# S7CAS-PLEIADES-CARTE-MERE_P07_CLOCK.net
KiCad netlist of a schematic drawn in Altium Designer
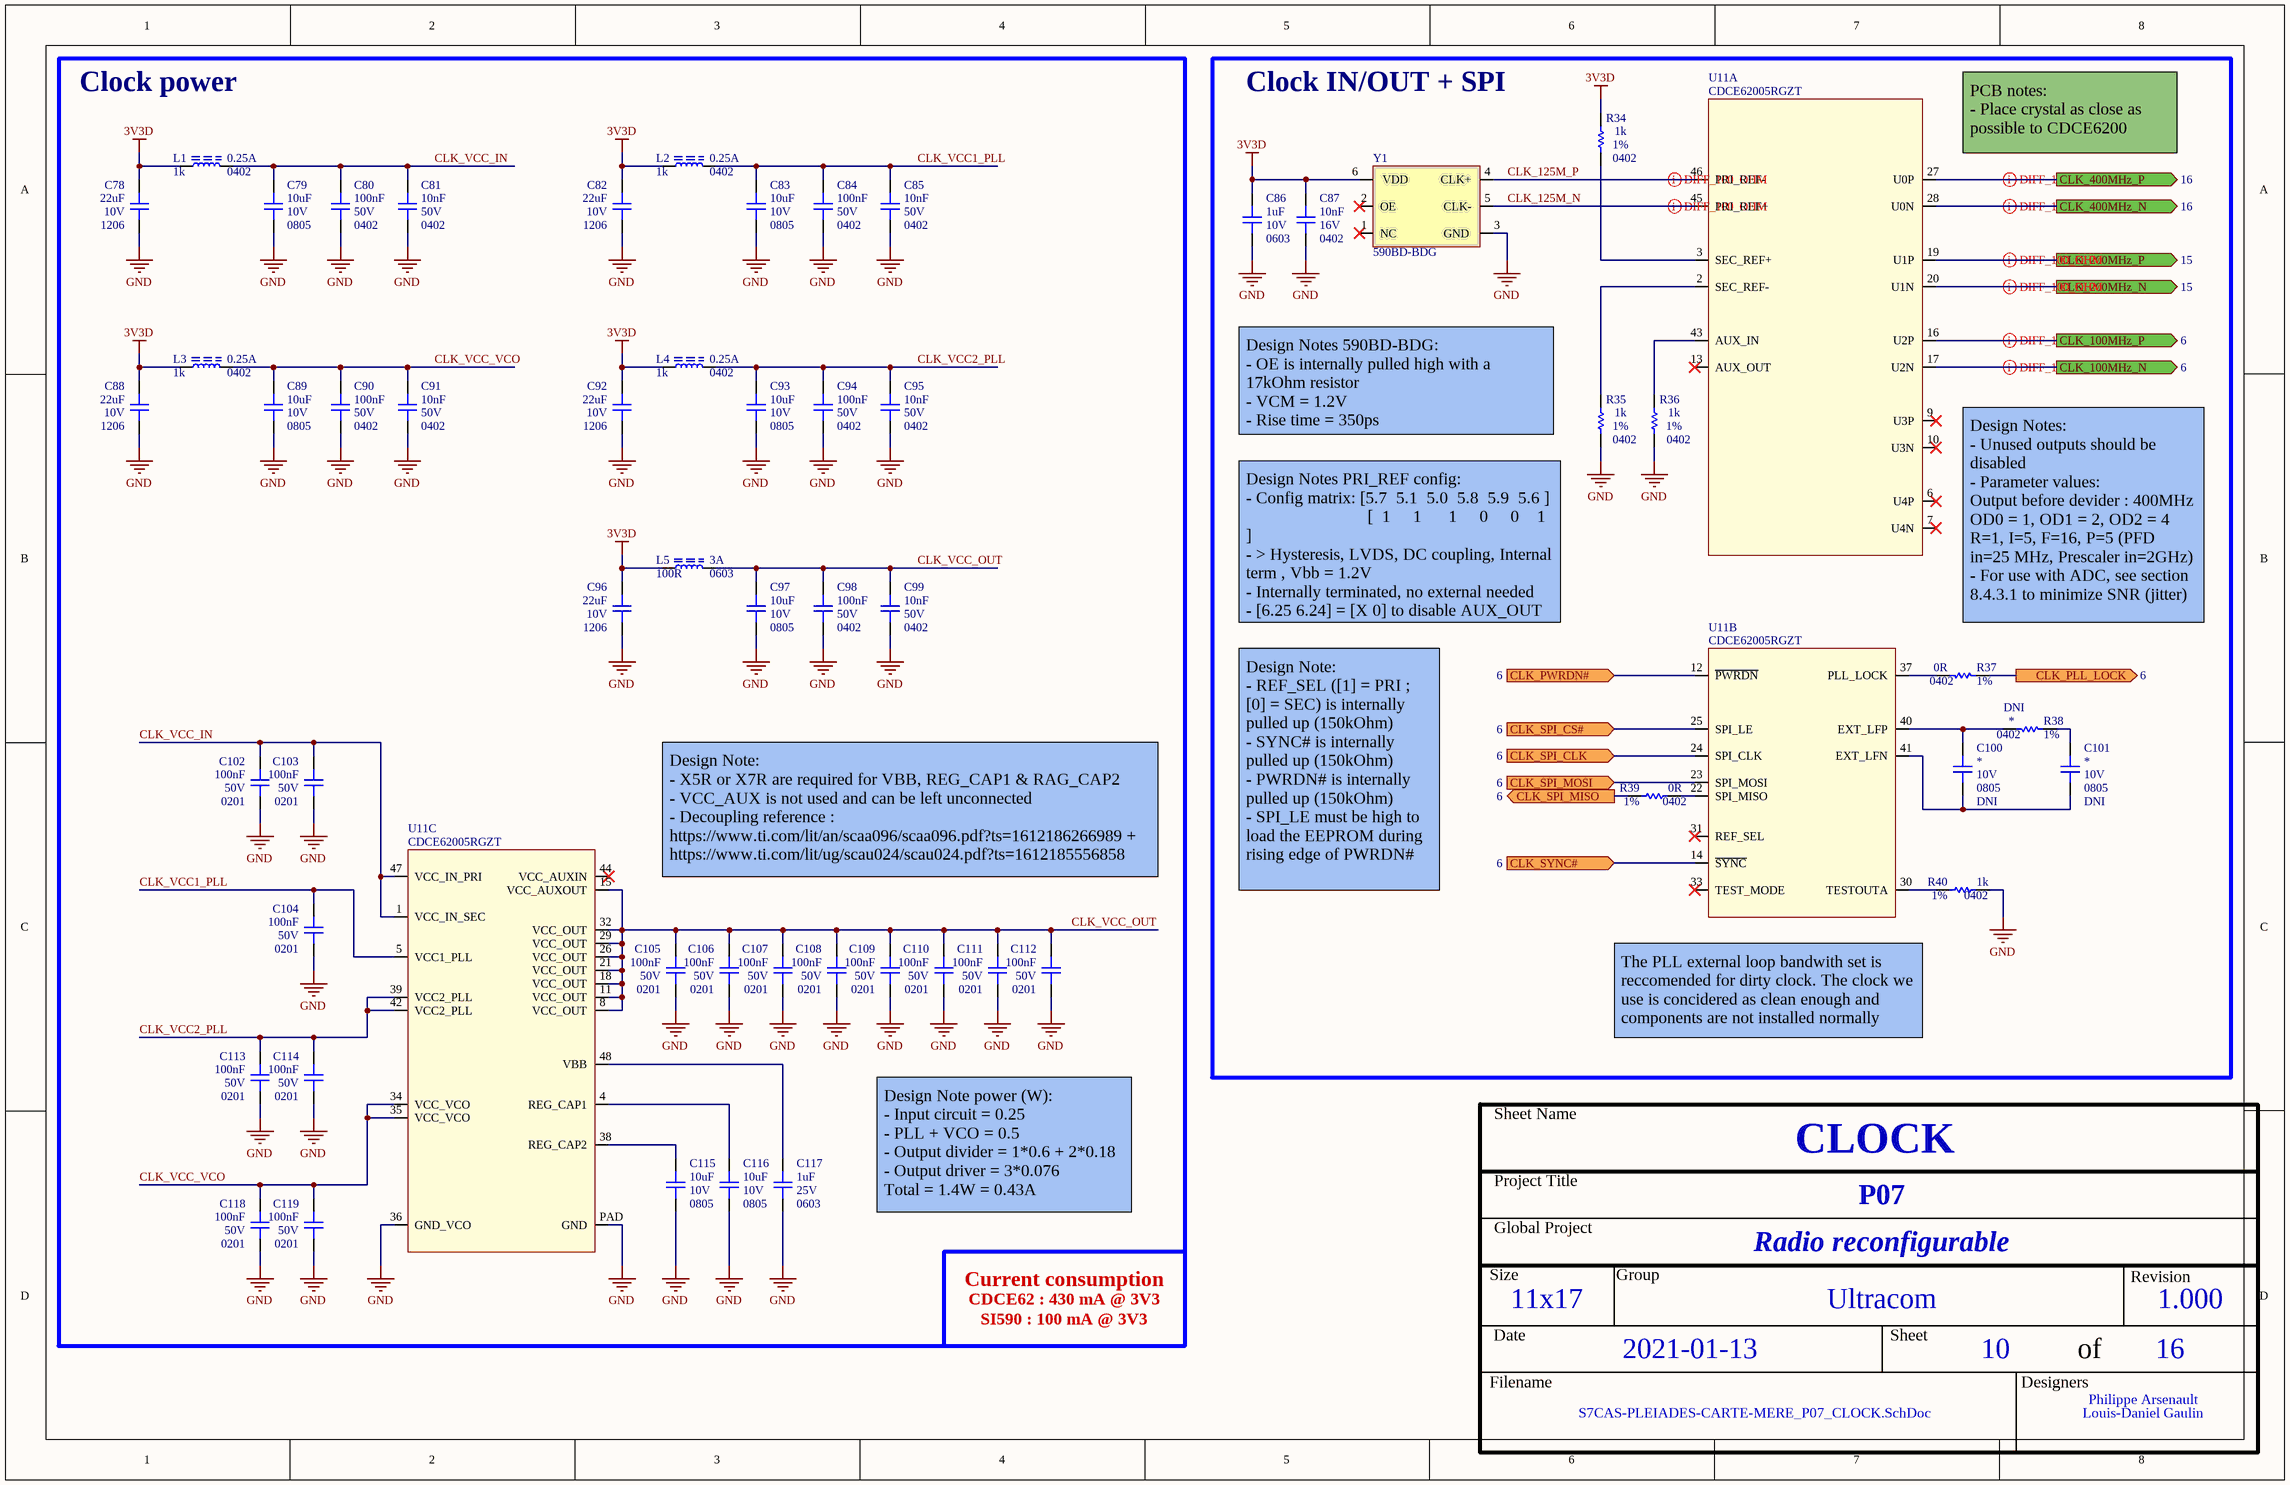
[diagram p0: S7CAS-PLEIADES-CARTE-MERE_P07_CLOCK.SchDoc]

(export (version "E")
  (design (tool "Eeschema 10.0.6"))
  (components
    (comp (ref "C78")
      (value "22uF")
      (footprint "CAP_1206")
      (description "CAP - 1206")
      (fields
        (field (name "VOLTAGE") "10V")
        (field (name "PACKAGE") "1206")
        (field (name "CREATEDBY") "Jonathan Bouchard")
      )
      (libsource (lib "S7CAS_LIB2021") (part "CAP - 1206"))
    )
    (comp (ref "C79")
      (value "10uF")
      (footprint "CAP_0805")
      (description "CAP - 0805")
      (fields
        (field (name "MFG") "CL21B106KPQNNNE")
        (field (name "VOLTAGE") "10V")
        (field (name "PACKAGE") "0805")
        (field (name "CREATEDBY") "Jonathan Bouchard")
      )
      (libsource (lib "S7CAS_LIB2021") (part "CAP - 0805"))
    )
    (comp (ref "C80")
      (value "100nF")
      (footprint "CAP_0402")
      (description "CAP - 0402")
      (fields
        (field (name "VOLTAGE") "50V")
        (field (name "PACKAGE") "0402")
        (field (name "CREATEDBY") "Jonathan Bouchard")
      )
      (libsource (lib "S7CAS_LIB2021") (part "CAP - 0402"))
    )
    (comp (ref "C81")
      (value "10nF")
      (footprint "CAP_0402")
      (description "CAP - 0402")
      (fields
        (field (name "VOLTAGE") "50V")
        (field (name "PACKAGE") "0402")
        (field (name "CREATEDBY") "Jonathan Bouchard")
      )
      (libsource (lib "S7CAS_LIB2021") (part "CAP - 0402"))
    )
    (comp (ref "C82")
      (value "22uF")
      (footprint "CAP_1206")
      (description "CAP - 1206")
      (fields
        (field (name "VOLTAGE") "10V")
        (field (name "PACKAGE") "1206")
        (field (name "CREATEDBY") "Jonathan Bouchard")
      )
      (libsource (lib "S7CAS_LIB2021") (part "CAP - 1206"))
    )
    (comp (ref "C83")
      (value "10uF")
      (footprint "CAP_0805")
      (description "CAP - 0805")
      (fields
        (field (name "MFG") "CL21B106KPQNNNE")
        (field (name "VOLTAGE") "10V")
        (field (name "PACKAGE") "0805")
        (field (name "CREATEDBY") "Jonathan Bouchard")
      )
      (libsource (lib "S7CAS_LIB2021") (part "CAP - 0805"))
    )
    (comp (ref "C84")
      (value "100nF")
      (footprint "CAP_0402")
      (description "CAP - 0402")
      (fields
        (field (name "VOLTAGE") "50V")
        (field (name "PACKAGE") "0402")
        (field (name "CREATEDBY") "Jonathan Bouchard")
      )
      (libsource (lib "S7CAS_LIB2021") (part "CAP - 0402"))
    )
    (comp (ref "C85")
      (value "10nF")
      (footprint "CAP_0402")
      (description "CAP - 0402")
      (fields
        (field (name "VOLTAGE") "50V")
        (field (name "PACKAGE") "0402")
        (field (name "CREATEDBY") "Jonathan Bouchard")
      )
      (libsource (lib "S7CAS_LIB2021") (part "CAP - 0402"))
    )
    (comp (ref "C86")
      (value "1uF")
      (footprint "CAP_0603")
      (description "CAP - 0603")
      (fields
        (field (name "VOLTAGE") "10V")
        (field (name "PACKAGE") "0603")
        (field (name "CREATEDBY") "Jonathan Bouchard")
      )
      (libsource (lib "S7CAS_LIB2021") (part "CAP - 0603"))
    )
    (comp (ref "C87")
      (value "10nF")
      (footprint "CAP_0402")
      (description "CAP - 0402")
      (fields
        (field (name "VOLTAGE") "16V")
        (field (name "PACKAGE") "0402")
        (field (name "CREATEDBY") "Jonathan Bouchard")
      )
      (libsource (lib "S7CAS_LIB2021") (part "CAP - 0402"))
    )
    (comp (ref "C88")
      (value "22uF")
      (footprint "CAP_1206")
      (description "CAP - 1206")
      (fields
        (field (name "VOLTAGE") "10V")
        (field (name "PACKAGE") "1206")
        (field (name "CREATEDBY") "Jonathan Bouchard")
      )
      (libsource (lib "S7CAS_LIB2021") (part "CAP - 1206"))
    )
    (comp (ref "C89")
      (value "10uF")
      (footprint "CAP_0805")
      (description "CAP - 0805")
      (fields
        (field (name "MFG") "CL21B106KPQNNNE")
        (field (name "VOLTAGE") "10V")
        (field (name "PACKAGE") "0805")
        (field (name "CREATEDBY") "Jonathan Bouchard")
      )
      (libsource (lib "S7CAS_LIB2021") (part "CAP - 0805"))
    )
    (comp (ref "C90")
      (value "100nF")
      (footprint "CAP_0402")
      (description "CAP - 0402")
      (fields
        (field (name "VOLTAGE") "50V")
        (field (name "PACKAGE") "0402")
        (field (name "CREATEDBY") "Jonathan Bouchard")
      )
      (libsource (lib "S7CAS_LIB2021") (part "CAP - 0402"))
    )
    (comp (ref "C91")
      (value "10nF")
      (footprint "CAP_0402")
      (description "CAP - 0402")
      (fields
        (field (name "VOLTAGE") "50V")
        (field (name "PACKAGE") "0402")
        (field (name "CREATEDBY") "Jonathan Bouchard")
      )
      (libsource (lib "S7CAS_LIB2021") (part "CAP - 0402"))
    )
    (comp (ref "C92")
      (value "22uF")
      (footprint "CAP_1206")
      (description "CAP - 1206")
      (fields
        (field (name "VOLTAGE") "10V")
        (field (name "PACKAGE") "1206")
        (field (name "CREATEDBY") "Jonathan Bouchard")
      )
      (libsource (lib "S7CAS_LIB2021") (part "CAP - 1206"))
    )
    (comp (ref "C93")
      (value "10uF")
      (footprint "CAP_0805")
      (description "CAP - 0805")
      (fields
        (field (name "MFG") "CL21B106KPQNNNE")
        (field (name "VOLTAGE") "10V")
        (field (name "PACKAGE") "0805")
        (field (name "CREATEDBY") "Jonathan Bouchard")
      )
      (libsource (lib "S7CAS_LIB2021") (part "CAP - 0805"))
    )
    (comp (ref "C94")
      (value "100nF")
      (footprint "CAP_0402")
      (description "CAP - 0402")
      (fields
        (field (name "VOLTAGE") "50V")
        (field (name "PACKAGE") "0402")
        (field (name "CREATEDBY") "Jonathan Bouchard")
      )
      (libsource (lib "S7CAS_LIB2021") (part "CAP - 0402"))
    )
    (comp (ref "C95")
      (value "10nF")
      (footprint "CAP_0402")
      (description "CAP - 0402")
      (fields
        (field (name "VOLTAGE") "50V")
        (field (name "PACKAGE") "0402")
        (field (name "CREATEDBY") "Jonathan Bouchard")
      )
      (libsource (lib "S7CAS_LIB2021") (part "CAP - 0402"))
    )
    (comp (ref "C96")
      (value "22uF")
      (footprint "CAP_1206")
      (description "CAP - 1206")
      (fields
        (field (name "VOLTAGE") "10V")
        (field (name "PACKAGE") "1206")
        (field (name "CREATEDBY") "Jonathan Bouchard")
      )
      (libsource (lib "S7CAS_LIB2021") (part "CAP - 1206"))
    )
    (comp (ref "C97")
      (value "10uF")
      (footprint "CAP_0805")
      (description "CAP - 0805")
      (fields
        (field (name "MFG") "CL21B106KPQNNNE")
        (field (name "VOLTAGE") "10V")
        (field (name "PACKAGE") "0805")
        (field (name "CREATEDBY") "Jonathan Bouchard")
      )
      (libsource (lib "S7CAS_LIB2021") (part "CAP - 0805"))
    )
    (comp (ref "C98")
      (value "100nF")
      (footprint "CAP_0402")
      (description "CAP - 0402")
      (fields
        (field (name "VOLTAGE") "50V")
        (field (name "PACKAGE") "0402")
        (field (name "CREATEDBY") "Jonathan Bouchard")
      )
      (libsource (lib "S7CAS_LIB2021") (part "CAP - 0402"))
    )
    (comp (ref "C99")
      (value "10nF")
      (footprint "CAP_0402")
      (description "CAP - 0402")
      (fields
        (field (name "VOLTAGE") "50V")
        (field (name "PACKAGE") "0402")
        (field (name "CREATEDBY") "Jonathan Bouchard")
      )
      (libsource (lib "S7CAS_LIB2021") (part "CAP - 0402"))
    )
    (comp (ref "C100")
      (value "CAP - 0805")
      (footprint "CAP_0805")
      (fields
        (field (name "MFG") "CL21B106KPQNNNE")
        (field (name "VOLTAGE") "10V")
        (field (name "NI") "DNI")
        (field (name "PACKAGE") "0805")
        (field (name "ALTIUM_VALUE") "*")
        (field (name "CREATEDBY") "Jonathan Bouchard")
      )
      (libsource (lib "S7CAS_LIB2021") (part "CAP - 0805"))
    )
    (comp (ref "C101")
      (value "CAP - 0805")
      (footprint "CAP_0805")
      (fields
        (field (name "MFG") "CL21B106KPQNNNE")
        (field (name "VOLTAGE") "10V")
        (field (name "NI") "DNI")
        (field (name "PACKAGE") "0805")
        (field (name "ALTIUM_VALUE") "*")
        (field (name "CREATEDBY") "Jonathan Bouchard")
      )
      (libsource (lib "S7CAS_LIB2021") (part "CAP - 0805"))
    )
    (comp (ref "C102")
      (value "100nF")
      (footprint "CAP_0201")
      (description "CAP - 0201")
      (fields
        (field (name "VOLTAGE") "50V")
        (field (name "PACKAGE") "0201")
        (field (name "CREATEDBY") "Jonathan Bouchard")
      )
      (libsource (lib "S7CAS_LIB2021") (part "CAP - 0201"))
    )
    (comp (ref "C103")
      (value "100nF")
      (footprint "CAP_0201")
      (description "CAP - 0201")
      (fields
        (field (name "VOLTAGE") "50V")
        (field (name "PACKAGE") "0201")
        (field (name "CREATEDBY") "Jonathan Bouchard")
      )
      (libsource (lib "S7CAS_LIB2021") (part "CAP - 0201"))
    )
    (comp (ref "C104")
      (value "100nF")
      (footprint "CAP_0201")
      (description "CAP - 0201")
      (fields
        (field (name "VOLTAGE") "50V")
        (field (name "PACKAGE") "0201")
        (field (name "CREATEDBY") "Jonathan Bouchard")
      )
      (libsource (lib "S7CAS_LIB2021") (part "CAP - 0201"))
    )
    (comp (ref "C105")
      (value "100nF")
      (footprint "CAP_0201")
      (description "CAP - 0201")
      (fields
        (field (name "VOLTAGE") "50V")
        (field (name "PACKAGE") "0201")
        (field (name "CREATEDBY") "Jonathan Bouchard")
      )
      (libsource (lib "S7CAS_LIB2021") (part "CAP - 0201"))
    )
    (comp (ref "C106")
      (value "100nF")
      (footprint "CAP_0201")
      (description "CAP - 0201")
      (fields
        (field (name "VOLTAGE") "50V")
        (field (name "PACKAGE") "0201")
        (field (name "CREATEDBY") "Jonathan Bouchard")
      )
      (libsource (lib "S7CAS_LIB2021") (part "CAP - 0201"))
    )
    (comp (ref "C107")
      (value "100nF")
      (footprint "CAP_0201")
      (description "CAP - 0201")
      (fields
        (field (name "VOLTAGE") "50V")
        (field (name "PACKAGE") "0201")
        (field (name "CREATEDBY") "Jonathan Bouchard")
      )
      (libsource (lib "S7CAS_LIB2021") (part "CAP - 0201"))
    )
    (comp (ref "C108")
      (value "100nF")
      (footprint "CAP_0201")
      (description "CAP - 0201")
      (fields
        (field (name "VOLTAGE") "50V")
        (field (name "PACKAGE") "0201")
        (field (name "CREATEDBY") "Jonathan Bouchard")
      )
      (libsource (lib "S7CAS_LIB2021") (part "CAP - 0201"))
    )
    (comp (ref "C109")
      (value "100nF")
      (footprint "CAP_0201")
      (description "CAP - 0201")
      (fields
        (field (name "VOLTAGE") "50V")
        (field (name "PACKAGE") "0201")
        (field (name "CREATEDBY") "Jonathan Bouchard")
      )
      (libsource (lib "S7CAS_LIB2021") (part "CAP - 0201"))
    )
    (comp (ref "C110")
      (value "100nF")
      (footprint "CAP_0201")
      (description "CAP - 0201")
      (fields
        (field (name "VOLTAGE") "50V")
        (field (name "PACKAGE") "0201")
        (field (name "CREATEDBY") "Jonathan Bouchard")
      )
      (libsource (lib "S7CAS_LIB2021") (part "CAP - 0201"))
    )
    (comp (ref "C111")
      (value "100nF")
      (footprint "CAP_0201")
      (description "CAP - 0201")
      (fields
        (field (name "VOLTAGE") "50V")
        (field (name "PACKAGE") "0201")
        (field (name "CREATEDBY") "Jonathan Bouchard")
      )
      (libsource (lib "S7CAS_LIB2021") (part "CAP - 0201"))
    )
    (comp (ref "C112")
      (value "100nF")
      (footprint "CAP_0201")
      (description "CAP - 0201")
      (fields
        (field (name "VOLTAGE") "50V")
        (field (name "PACKAGE") "0201")
        (field (name "CREATEDBY") "Jonathan Bouchard")
      )
      (libsource (lib "S7CAS_LIB2021") (part "CAP - 0201"))
    )
    (comp (ref "C113")
      (value "100nF")
      (footprint "CAP_0201")
      (description "CAP - 0201")
      (fields
        (field (name "VOLTAGE") "50V")
        (field (name "PACKAGE") "0201")
        (field (name "CREATEDBY") "Jonathan Bouchard")
      )
      (libsource (lib "S7CAS_LIB2021") (part "CAP - 0201"))
    )
    (comp (ref "C114")
      (value "100nF")
      (footprint "CAP_0201")
      (description "CAP - 0201")
      (fields
        (field (name "VOLTAGE") "50V")
        (field (name "PACKAGE") "0201")
        (field (name "CREATEDBY") "Jonathan Bouchard")
      )
      (libsource (lib "S7CAS_LIB2021") (part "CAP - 0201"))
    )
    (comp (ref "C115")
      (value "10uF")
      (footprint "CAP_0805")
      (description "CAP - 0805")
      (fields
        (field (name "MFG") "CL21B106KPQNNNE")
        (field (name "VOLTAGE") "10V")
        (field (name "PACKAGE") "0805")
        (field (name "CREATEDBY") "Jonathan Bouchard")
      )
      (libsource (lib "S7CAS_LIB2021") (part "CAP - 0805"))
    )
    (comp (ref "C116")
      (value "10uF")
      (footprint "CAP_0805")
      (description "CAP - 0805")
      (fields
        (field (name "MFG") "CL21B106KPQNNNE")
        (field (name "VOLTAGE") "10V")
        (field (name "PACKAGE") "0805")
        (field (name "CREATEDBY") "Jonathan Bouchard")
      )
      (libsource (lib "S7CAS_LIB2021") (part "CAP - 0805"))
    )
    (comp (ref "C117")
      (value "1uF")
      (footprint "CAP_0603")
      (description "CAP - 0603")
      (fields
        (field (name "MFG PART NUMBER") "CC0603KRX5R8BB105")
        (field (name "VOLTAGE") "25V")
        (field (name "PACKAGE") "0603")
        (field (name "CREATEDBY") "Jonathan Bouchard")
      )
      (libsource (lib "S7CAS_LIB2021") (part "CAP - 0603"))
    )
    (comp (ref "C118")
      (value "100nF")
      (footprint "CAP_0201")
      (description "CAP - 0201")
      (fields
        (field (name "VOLTAGE") "50V")
        (field (name "PACKAGE") "0201")
        (field (name "CREATEDBY") "Jonathan Bouchard")
      )
      (libsource (lib "S7CAS_LIB2021") (part "CAP - 0201"))
    )
    (comp (ref "C119")
      (value "100nF")
      (footprint "CAP_0201")
      (description "CAP - 0201")
      (fields
        (field (name "VOLTAGE") "50V")
        (field (name "PACKAGE") "0201")
        (field (name "CREATEDBY") "Jonathan Bouchard")
      )
      (libsource (lib "S7CAS_LIB2021") (part "CAP - 0201"))
    )
    (comp (ref "L1")
      (value "1k")
      (footprint "FER_0402")
      (description "FER - 0402")
      (fields
        (field (name "MFG PART NUMBER") "BLM15HD102SN1D")
        (field (name "CURRENT") "0.25A")
        (field (name "PACKAGE") "0402")
        (field (name "CREATEDBY") "Jonathan Bouchard")
      )
      (libsource (lib "S7CAS_LIB2021") (part "FER - 0402"))
    )
    (comp (ref "L2")
      (value "1k")
      (footprint "FER_0402")
      (description "FER - 0402")
      (fields
        (field (name "MFG PART NUMBER") "BLM15HD102SN1D")
        (field (name "CURRENT") "0.25A")
        (field (name "PACKAGE") "0402")
        (field (name "CREATEDBY") "Jonathan Bouchard")
      )
      (libsource (lib "S7CAS_LIB2021") (part "FER - 0402"))
    )
    (comp (ref "L3")
      (value "1k")
      (footprint "FER_0402")
      (description "FER - 0402")
      (fields
        (field (name "MFG PART NUMBER") "BLM15HD102SN1D")
        (field (name "CURRENT") "0.25A")
        (field (name "PACKAGE") "0402")
        (field (name "CREATEDBY") "Jonathan Bouchard")
      )
      (libsource (lib "S7CAS_LIB2021") (part "FER - 0402"))
    )
    (comp (ref "L4")
      (value "1k")
      (footprint "FER_0402")
      (description "FER - 0402")
      (fields
        (field (name "MFG PART NUMBER") "BLM15HD102SN1D")
        (field (name "CURRENT") "0.25A")
        (field (name "PACKAGE") "0402")
        (field (name "CREATEDBY") "Jonathan Bouchard")
      )
      (libsource (lib "S7CAS_LIB2021") (part "FER - 0402"))
    )
    (comp (ref "L5")
      (value "100R")
      (footprint "FER_0603")
      (description "FER - 0603")
      (fields
        (field (name "MFG PART NUMBER") "BLM18KG101TN1D")
        (field (name "CURRENT") "3A")
        (field (name "PACKAGE") "0603")
        (field (name "CREATEDBY") "Jonathan Bouchard")
      )
      (libsource (lib "S7CAS_LIB2021") (part "FER - 0603"))
    )
    (comp (ref "R34")
      (value "1k")
      (footprint "RES_0402")
      (description "RES - 0402")
      (fields
        (field (name "VOLTAGE") "50V")
        (field (name "POWER") "1/16W")
        (field (name "PACKAGE") "0402")
        (field (name "PRECISION") "1%")
        (field (name "CREATEDBY") "Jonathan Bouchard")
      )
      (libsource (lib "S7CAS_LIB2021") (part "RES - 0402"))
    )
    (comp (ref "R35")
      (value "1k")
      (footprint "RES_0402")
      (description "RES - 0402")
      (fields
        (field (name "VOLTAGE") "50V")
        (field (name "POWER") "1/16W")
        (field (name "PACKAGE") "0402")
        (field (name "PRECISION") "1%")
        (field (name "CREATEDBY") "Jonathan Bouchard")
      )
      (libsource (lib "S7CAS_LIB2021") (part "RES - 0402"))
    )
    (comp (ref "R36")
      (value "1k")
      (footprint "RES_0402")
      (description "RES - 0402")
      (fields
        (field (name "VOLTAGE") "50V")
        (field (name "POWER") "1/16W")
        (field (name "PACKAGE") "0402")
        (field (name "PRECISION") "1%")
        (field (name "CREATEDBY") "Jonathan Bouchard")
      )
      (libsource (lib "S7CAS_LIB2021") (part "RES - 0402"))
    )
    (comp (ref "R37")
      (value "0R")
      (footprint "RES_0402")
      (description "RES - 0402")
      (fields
        (field (name "VOLTAGE") "50V")
        (field (name "POWER") "1/16W")
        (field (name "PACKAGE") "0402")
        (field (name "PRECISION") "1%")
        (field (name "CREATEDBY") "Jonathan Bouchard")
      )
      (libsource (lib "S7CAS_LIB2021") (part "RES - 0402"))
    )
    (comp (ref "R38")
      (value "RES - 0402")
      (footprint "RES_0402")
      (fields
        (field (name "VOLTAGE") "50V")
        (field (name "POWER") "1/16W")
        (field (name "NI") "DNI")
        (field (name "PACKAGE") "0402")
        (field (name "PRECISION") "1%")
        (field (name "ALTIUM_VALUE") "*")
        (field (name "CREATEDBY") "Jonathan Bouchard")
      )
      (libsource (lib "S7CAS_LIB2021") (part "RES - 0402"))
    )
    (comp (ref "R39")
      (value "0R")
      (footprint "RES_0402")
      (description "RES - 0402")
      (fields
        (field (name "VOLTAGE") "50V")
        (field (name "POWER") "1/16W")
        (field (name "PACKAGE") "0402")
        (field (name "PRECISION") "1%")
        (field (name "CREATEDBY") "Jonathan Bouchard")
      )
      (libsource (lib "S7CAS_LIB2021") (part "RES - 0402"))
    )
    (comp (ref "R40")
      (value "1k")
      (footprint "RES_0402")
      (description "RES - 0402")
      (fields
        (field (name "VOLTAGE") "50V")
        (field (name "POWER") "1/16W")
        (field (name "PACKAGE") "0402")
        (field (name "PRECISION") "1%")
        (field (name "CREATEDBY") "Jonathan Bouchard")
      )
      (libsource (lib "S7CAS_LIB2021") (part "RES - 0402"))
    )
    (comp (ref "U11")
      (value "CDCE62005RGZT")
      (footprint "TIM_CDCE62005RGZT")
      (description "TIM - CLK SYNTH JITTER CLEANER 3:5 - QFN-48")
      (fields
        (field (name "VOLTAGE") "3 V ~ 3.6 V")
        (field (name "MFG") "Texas Instruments")
        (field (name "CREATEDBY") "Jonathan Bouchard")
      )
      (libsource (lib "S7CAS_LIB2021") (part "TIM_CDCE62005RGZT"))
    )
    (comp (ref "Y1")
      (value "590BD-BDG")
      (footprint "OSC_590BD-BDG")
      (description "TIM - OSC PROG 125MHz ~ 214.999MHz LVDS 3.3V 7PPM EN/DS - 6-SMD")
      (fields
        (field (name "CREATEDBY/DATE") "from 590BD-CDG")
        (field (name "VERIFIEDBY") "Caroline Paulin / 3/10/2019")
      )
      (libsource (lib "S7CAS_LIB2021") (part "OSC_590BD-BDG"))
    )
  )
  (nets
    (net (code "1") (name "/CLK_100MHz_N") (class "Default")
      (node (ref "U11") (pin "17") (pinfunction "U2N_17") (pintype "passive"))
    )
    (net (code "2") (name "/CLK_100MHz_P") (class "Default")
      (node (ref "U11") (pin "16") (pinfunction "U2P_16") (pintype "passive"))
    )
    (net (code "3") (name "/CLK_125M_N") (class "Default")
      (node (ref "U11") (pin "45") (pinfunction "PRI_REF+_45") (pintype "passive"))
      (node (ref "Y1") (pin "5") (pinfunction "CLK-_5") (pintype "passive"))
    )
    (net (code "4") (name "/CLK_125M_P") (class "Default")
      (node (ref "U11") (pin "46") (pinfunction "PRI_REF-_46") (pintype "passive"))
      (node (ref "Y1") (pin "4") (pinfunction "CLK+_4") (pintype "passive"))
    )
    (net (code "5") (name "/CLK_200MHz_N") (class "Default")
      (node (ref "U11") (pin "20") (pinfunction "U1N_20") (pintype "passive"))
    )
    (net (code "6") (name "/CLK_200MHz_P") (class "Default")
      (node (ref "U11") (pin "19") (pinfunction "U1P_19") (pintype "passive"))
    )
    (net (code "7") (name "/CLK_400MHz_N") (class "Default")
      (node (ref "U11") (pin "28") (pinfunction "U0N_28") (pintype "passive"))
    )
    (net (code "8") (name "/CLK_400MHz_P") (class "Default")
      (node (ref "U11") (pin "27") (pinfunction "U0P_27") (pintype "passive"))
    )
    (net (code "9") (name "/CLK_PLL_LOCK") (class "Default")
      (node (ref "R37") (pin "2") (pinfunction "2_2") (pintype "passive"))
    )
    (net (code "10") (name "/CLK_PWRDN#") (class "Default")
      (node (ref "U11") (pin "12") (pinfunction "~{PWRDN}_12") (pintype "passive"))
    )
    (net (code "11") (name "/CLK_SPI_CLK") (class "Default")
      (node (ref "U11") (pin "24") (pinfunction "SPI_CLK_24") (pintype "passive"))
    )
    (net (code "12") (name "/CLK_SPI_CS#") (class "Default")
      (node (ref "U11") (pin "25") (pinfunction "SPI_LE_25") (pintype "passive"))
    )
    (net (code "13") (name "/CLK_SPI_MISO") (class "Default")
      (node (ref "R39") (pin "2") (pinfunction "2_2") (pintype "passive"))
    )
    (net (code "14") (name "/CLK_SPI_MOSI") (class "Default")
      (node (ref "U11") (pin "23") (pinfunction "SPI_MOSI_23") (pintype "passive"))
    )
    (net (code "15") (name "/CLK_SYNC#") (class "Default")
      (node (ref "U11") (pin "14") (pinfunction "~{SYNC}_14") (pintype "passive"))
    )
    (net (code "16") (name "/CLK_VCC1_PLL") (class "Default")
      (node (ref "C104") (pin "2") (pinfunction "2_2") (pintype "passive"))
      (node (ref "C83") (pin "2") (pinfunction "2_2") (pintype "passive"))
      (node (ref "C84") (pin "2") (pinfunction "2_2") (pintype "passive"))
      (node (ref "C85") (pin "2") (pinfunction "2_2") (pintype "passive"))
      (node (ref "L2") (pin "1") (pinfunction "1_1") (pintype "passive"))
      (node (ref "U11") (pin "5") (pinfunction "VCC1_PLL_5") (pintype "passive"))
    )
    (net (code "17") (name "/CLK_VCC2_PLL") (class "Default")
      (node (ref "C113") (pin "2") (pinfunction "2_2") (pintype "passive"))
      (node (ref "C114") (pin "2") (pinfunction "2_2") (pintype "passive"))
      (node (ref "C93") (pin "2") (pinfunction "2_2") (pintype "passive"))
      (node (ref "C94") (pin "2") (pinfunction "2_2") (pintype "passive"))
      (node (ref "C95") (pin "2") (pinfunction "2_2") (pintype "passive"))
      (node (ref "L4") (pin "1") (pinfunction "1_1") (pintype "passive"))
      (node (ref "U11") (pin "39") (pinfunction "VCC2_PLL_39") (pintype "passive"))
      (node (ref "U11") (pin "42") (pinfunction "VCC2_PLL_42") (pintype "passive"))
    )
    (net (code "18") (name "/CLK_VCC_IN") (class "Default")
      (node (ref "C102") (pin "2") (pinfunction "2_2") (pintype "passive"))
      (node (ref "C103") (pin "2") (pinfunction "2_2") (pintype "passive"))
      (node (ref "C79") (pin "2") (pinfunction "2_2") (pintype "passive"))
      (node (ref "C80") (pin "2") (pinfunction "2_2") (pintype "passive"))
      (node (ref "C81") (pin "2") (pinfunction "2_2") (pintype "passive"))
      (node (ref "L1") (pin "1") (pinfunction "1_1") (pintype "passive"))
      (node (ref "U11") (pin "1") (pinfunction "VCC_IN_SEC_1") (pintype "passive"))
      (node (ref "U11") (pin "47") (pinfunction "VCC_IN_PRI_47") (pintype "passive"))
    )
    (net (code "19") (name "/CLK_VCC_OUT") (class "Default")
      (node (ref "C105") (pin "2") (pinfunction "2_2") (pintype "passive"))
      (node (ref "C106") (pin "2") (pinfunction "2_2") (pintype "passive"))
      (node (ref "C107") (pin "2") (pinfunction "2_2") (pintype "passive"))
      (node (ref "C108") (pin "2") (pinfunction "2_2") (pintype "passive"))
      (node (ref "C109") (pin "2") (pinfunction "2_2") (pintype "passive"))
      (node (ref "C110") (pin "2") (pinfunction "2_2") (pintype "passive"))
      (node (ref "C111") (pin "2") (pinfunction "2_2") (pintype "passive"))
      (node (ref "C112") (pin "2") (pinfunction "2_2") (pintype "passive"))
      (node (ref "C97") (pin "2") (pinfunction "2_2") (pintype "passive"))
      (node (ref "C98") (pin "2") (pinfunction "2_2") (pintype "passive"))
      (node (ref "C99") (pin "2") (pinfunction "2_2") (pintype "passive"))
      (node (ref "L5") (pin "1") (pinfunction "1_1") (pintype "passive"))
      (node (ref "U11") (pin "11") (pinfunction "VCC_OUT_11") (pintype "passive"))
      (node (ref "U11") (pin "15") (pinfunction "VCC_AUXOUT_15") (pintype "passive"))
      (node (ref "U11") (pin "18") (pinfunction "VCC_OUT_18") (pintype "passive"))
      (node (ref "U11") (pin "21") (pinfunction "VCC_OUT_21") (pintype "passive"))
      (node (ref "U11") (pin "26") (pinfunction "VCC_OUT_26") (pintype "passive"))
      (node (ref "U11") (pin "29") (pinfunction "VCC_OUT_29") (pintype "passive"))
      (node (ref "U11") (pin "32") (pinfunction "VCC_OUT_32") (pintype "passive"))
      (node (ref "U11") (pin "8") (pinfunction "VCC_OUT_8") (pintype "passive"))
    )
    (net (code "20") (name "/CLK_VCC_VCO") (class "Default")
      (node (ref "C118") (pin "2") (pinfunction "2_2") (pintype "passive"))
      (node (ref "C119") (pin "2") (pinfunction "2_2") (pintype "passive"))
      (node (ref "C89") (pin "2") (pinfunction "2_2") (pintype "passive"))
      (node (ref "C90") (pin "2") (pinfunction "2_2") (pintype "passive"))
      (node (ref "C91") (pin "2") (pinfunction "2_2") (pintype "passive"))
      (node (ref "L3") (pin "1") (pinfunction "1_1") (pintype "passive"))
      (node (ref "U11") (pin "34") (pinfunction "VCC_VCO_34") (pintype "passive"))
      (node (ref "U11") (pin "35") (pinfunction "VCC_VCO_35") (pintype "passive"))
    )
    (net (code "21") (name "3V3D") (class "Default")
      (node (ref "C78") (pin "2") (pinfunction "2_2") (pintype "passive"))
      (node (ref "C82") (pin "2") (pinfunction "2_2") (pintype "passive"))
      (node (ref "C86") (pin "2") (pinfunction "2_2") (pintype "passive"))
      (node (ref "C87") (pin "2") (pinfunction "2_2") (pintype "passive"))
      (node (ref "C88") (pin "2") (pinfunction "2_2") (pintype "passive"))
      (node (ref "C92") (pin "2") (pinfunction "2_2") (pintype "passive"))
      (node (ref "C96") (pin "2") (pinfunction "2_2") (pintype "passive"))
      (node (ref "L1") (pin "2") (pinfunction "2_2") (pintype "passive"))
      (node (ref "L2") (pin "2") (pinfunction "2_2") (pintype "passive"))
      (node (ref "L3") (pin "2") (pinfunction "2_2") (pintype "passive"))
      (node (ref "L4") (pin "2") (pinfunction "2_2") (pintype "passive"))
      (node (ref "L5") (pin "2") (pinfunction "2_2") (pintype "passive"))
      (node (ref "R34") (pin "2") (pinfunction "2_2") (pintype "passive"))
      (node (ref "Y1") (pin "6") (pinfunction "VDD_6") (pintype "passive"))
    )
    (net (code "22") (name "GND") (class "Default")
      (node (ref "C102") (pin "1") (pinfunction "1_1") (pintype "passive"))
      (node (ref "C103") (pin "1") (pinfunction "1_1") (pintype "passive"))
      (node (ref "C104") (pin "1") (pinfunction "1_1") (pintype "passive"))
      (node (ref "C105") (pin "1") (pinfunction "1_1") (pintype "passive"))
      (node (ref "C106") (pin "1") (pinfunction "1_1") (pintype "passive"))
      (node (ref "C107") (pin "1") (pinfunction "1_1") (pintype "passive"))
      (node (ref "C108") (pin "1") (pinfunction "1_1") (pintype "passive"))
      (node (ref "C109") (pin "1") (pinfunction "1_1") (pintype "passive"))
      (node (ref "C110") (pin "1") (pinfunction "1_1") (pintype "passive"))
      (node (ref "C111") (pin "1") (pinfunction "1_1") (pintype "passive"))
      (node (ref "C112") (pin "1") (pinfunction "1_1") (pintype "passive"))
      (node (ref "C113") (pin "1") (pinfunction "1_1") (pintype "passive"))
      (node (ref "C114") (pin "1") (pinfunction "1_1") (pintype "passive"))
      (node (ref "C115") (pin "1") (pinfunction "1_1") (pintype "passive"))
      (node (ref "C116") (pin "1") (pinfunction "1_1") (pintype "passive"))
      (node (ref "C117") (pin "1") (pinfunction "1_1") (pintype "passive"))
      (node (ref "C118") (pin "1") (pinfunction "1_1") (pintype "passive"))
      (node (ref "C119") (pin "1") (pinfunction "1_1") (pintype "passive"))
      (node (ref "C78") (pin "1") (pinfunction "1_1") (pintype "passive"))
      (node (ref "C79") (pin "1") (pinfunction "1_1") (pintype "passive"))
      (node (ref "C80") (pin "1") (pinfunction "1_1") (pintype "passive"))
      (node (ref "C81") (pin "1") (pinfunction "1_1") (pintype "passive"))
      (node (ref "C82") (pin "1") (pinfunction "1_1") (pintype "passive"))
      (node (ref "C83") (pin "1") (pinfunction "1_1") (pintype "passive"))
      (node (ref "C84") (pin "1") (pinfunction "1_1") (pintype "passive"))
      (node (ref "C85") (pin "1") (pinfunction "1_1") (pintype "passive"))
      (node (ref "C86") (pin "1") (pinfunction "1_1") (pintype "passive"))
      (node (ref "C87") (pin "1") (pinfunction "1_1") (pintype "passive"))
      (node (ref "C88") (pin "1") (pinfunction "1_1") (pintype "passive"))
      (node (ref "C89") (pin "1") (pinfunction "1_1") (pintype "passive"))
      (node (ref "C90") (pin "1") (pinfunction "1_1") (pintype "passive"))
      (node (ref "C91") (pin "1") (pinfunction "1_1") (pintype "passive"))
      (node (ref "C92") (pin "1") (pinfunction "1_1") (pintype "passive"))
      (node (ref "C93") (pin "1") (pinfunction "1_1") (pintype "passive"))
      (node (ref "C94") (pin "1") (pinfunction "1_1") (pintype "passive"))
      (node (ref "C95") (pin "1") (pinfunction "1_1") (pintype "passive"))
      (node (ref "C96") (pin "1") (pinfunction "1_1") (pintype "passive"))
      (node (ref "C97") (pin "1") (pinfunction "1_1") (pintype "passive"))
      (node (ref "C98") (pin "1") (pinfunction "1_1") (pintype "passive"))
      (node (ref "C99") (pin "1") (pinfunction "1_1") (pintype "passive"))
      (node (ref "R35") (pin "1") (pinfunction "1_1") (pintype "passive"))
      (node (ref "R36") (pin "1") (pinfunction "1_1") (pintype "passive"))
      (node (ref "R40") (pin "1") (pinfunction "1_1") (pintype "passive"))
      (node (ref "U11") (pin "36") (pinfunction "GND_VCO_36") (pintype "passive"))
      (node (ref "U11") (pin "PAD") (pinfunction "GND_PAD") (pintype "passive"))
      (node (ref "Y1") (pin "3") (pinfunction "GND_3") (pintype "passive"))
    )
    (net (code "23") (name "Net-(C101-Pad2)") (class "Default")
      (node (ref "C101") (pin "2") (pinfunction "2_2") (pintype "passive"))
      (node (ref "R38") (pin "2") (pinfunction "2_2") (pintype "passive"))
    )
    (net (code "24") (name "Net-(U11A-AUX_IN)") (class "Default")
      (node (ref "R36") (pin "2") (pinfunction "2_2") (pintype "passive"))
      (node (ref "U11") (pin "43") (pinfunction "AUX_IN_43") (pintype "passive"))
    )
    (net (code "25") (name "Net-(U11A-SEC_REF+)") (class "Default")
      (node (ref "R34") (pin "1") (pinfunction "1_1") (pintype "passive"))
      (node (ref "U11") (pin "3") (pinfunction "SEC_REF+_3") (pintype "passive"))
    )
    (net (code "26") (name "Net-(U11A-SEC_REF-)") (class "Default")
      (node (ref "R35") (pin "2") (pinfunction "2_2") (pintype "passive"))
      (node (ref "U11") (pin "2") (pinfunction "SEC_REF-_2") (pintype "passive"))
    )
    (net (code "27") (name "Net-(U11B-EXT_LFN)") (class "Default")
      (node (ref "C100") (pin "1") (pinfunction "1_1") (pintype "passive"))
      (node (ref "C101") (pin "1") (pinfunction "1_1") (pintype "passive"))
      (node (ref "U11") (pin "41") (pinfunction "EXT_LFN_41") (pintype "passive"))
    )
    (net (code "28") (name "Net-(U11B-EXT_LFP)") (class "Default")
      (node (ref "C100") (pin "2") (pinfunction "2_2") (pintype "passive"))
      (node (ref "R38") (pin "1") (pinfunction "1_1") (pintype "passive"))
      (node (ref "U11") (pin "40") (pinfunction "EXT_LFP_40") (pintype "passive"))
    )
    (net (code "29") (name "Net-(U11B-PLL_LOCK)") (class "Default")
      (node (ref "R37") (pin "1") (pinfunction "1_1") (pintype "passive"))
      (node (ref "U11") (pin "37") (pinfunction "PLL_LOCK_37") (pintype "passive"))
    )
    (net (code "30") (name "Net-(U11B-SPI_MISO)") (class "Default")
      (node (ref "R39") (pin "1") (pinfunction "1_1") (pintype "passive"))
      (node (ref "U11") (pin "22") (pinfunction "SPI_MISO_22") (pintype "passive"))
    )
    (net (code "31") (name "Net-(U11B-TESTOUTA)") (class "Default")
      (node (ref "R40") (pin "2") (pinfunction "2_2") (pintype "passive"))
      (node (ref "U11") (pin "30") (pinfunction "TESTOUTA_30") (pintype "passive"))
    )
    (net (code "32") (name "Net-(U11C-REG_CAP1)") (class "Default")
      (node (ref "C116") (pin "2") (pinfunction "2_2") (pintype "passive"))
      (node (ref "U11") (pin "4") (pinfunction "REG_CAP1_4") (pintype "passive"))
    )
    (net (code "33") (name "Net-(U11C-REG_CAP2)") (class "Default")
      (node (ref "C115") (pin "2") (pinfunction "2_2") (pintype "passive"))
      (node (ref "U11") (pin "38") (pinfunction "REG_CAP2_38") (pintype "passive"))
    )
    (net (code "34") (name "Net-(U11C-VBB)") (class "Default")
      (node (ref "C117") (pin "2") (pinfunction "2_2") (pintype "passive"))
      (node (ref "U11") (pin "48") (pinfunction "VBB_48") (pintype "passive"))
    )
    (net (code "35") (name "unconnected-(U11A-AUX_OUT-Pad13)") (class "Default")
      (node (ref "U11") (pin "13") (pinfunction "AUX_OUT_13") (pintype "passive+no_connect"))
    )
    (net (code "36") (name "unconnected-(U11A-U3N-Pad10)") (class "Default")
      (node (ref "U11") (pin "10") (pinfunction "U3N_10") (pintype "passive+no_connect"))
    )
    (net (code "37") (name "unconnected-(U11A-U3P-Pad9)") (class "Default")
      (node (ref "U11") (pin "9") (pinfunction "U3P_9") (pintype "passive+no_connect"))
    )
    (net (code "38") (name "unconnected-(U11A-U4N-Pad7)") (class "Default")
      (node (ref "U11") (pin "7") (pinfunction "U4N_7") (pintype "passive+no_connect"))
    )
    (net (code "39") (name "unconnected-(U11A-U4P-Pad6)") (class "Default")
      (node (ref "U11") (pin "6") (pinfunction "U4P_6") (pintype "passive+no_connect"))
    )
    (net (code "40") (name "unconnected-(U11B-REF_SEL-Pad31)") (class "Default")
      (node (ref "U11") (pin "31") (pinfunction "REF_SEL_31") (pintype "passive+no_connect"))
    )
    (net (code "41") (name "unconnected-(U11B-TEST_MODE-Pad33)") (class "Default")
      (node (ref "U11") (pin "33") (pinfunction "TEST_MODE_33") (pintype "passive+no_connect"))
    )
    (net (code "42") (name "unconnected-(U11C-VCC_AUXIN-Pad44)") (class "Default")
      (node (ref "U11") (pin "44") (pinfunction "VCC_AUXIN_44") (pintype "passive+no_connect"))
    )
    (net (code "43") (name "unconnected-(Y1-NC-Pad1)") (class "Default")
      (node (ref "Y1") (pin "1") (pinfunction "NC_1") (pintype "passive+no_connect"))
    )
    (net (code "44") (name "unconnected-(Y1-OE-Pad2)") (class "Default")
      (node (ref "Y1") (pin "2") (pinfunction "OE_2") (pintype "passive+no_connect"))
    )
  )
)
